# Mini_Ultra_Base_Shield.net
KiCad netlist of a schematic drawn in EAGLE
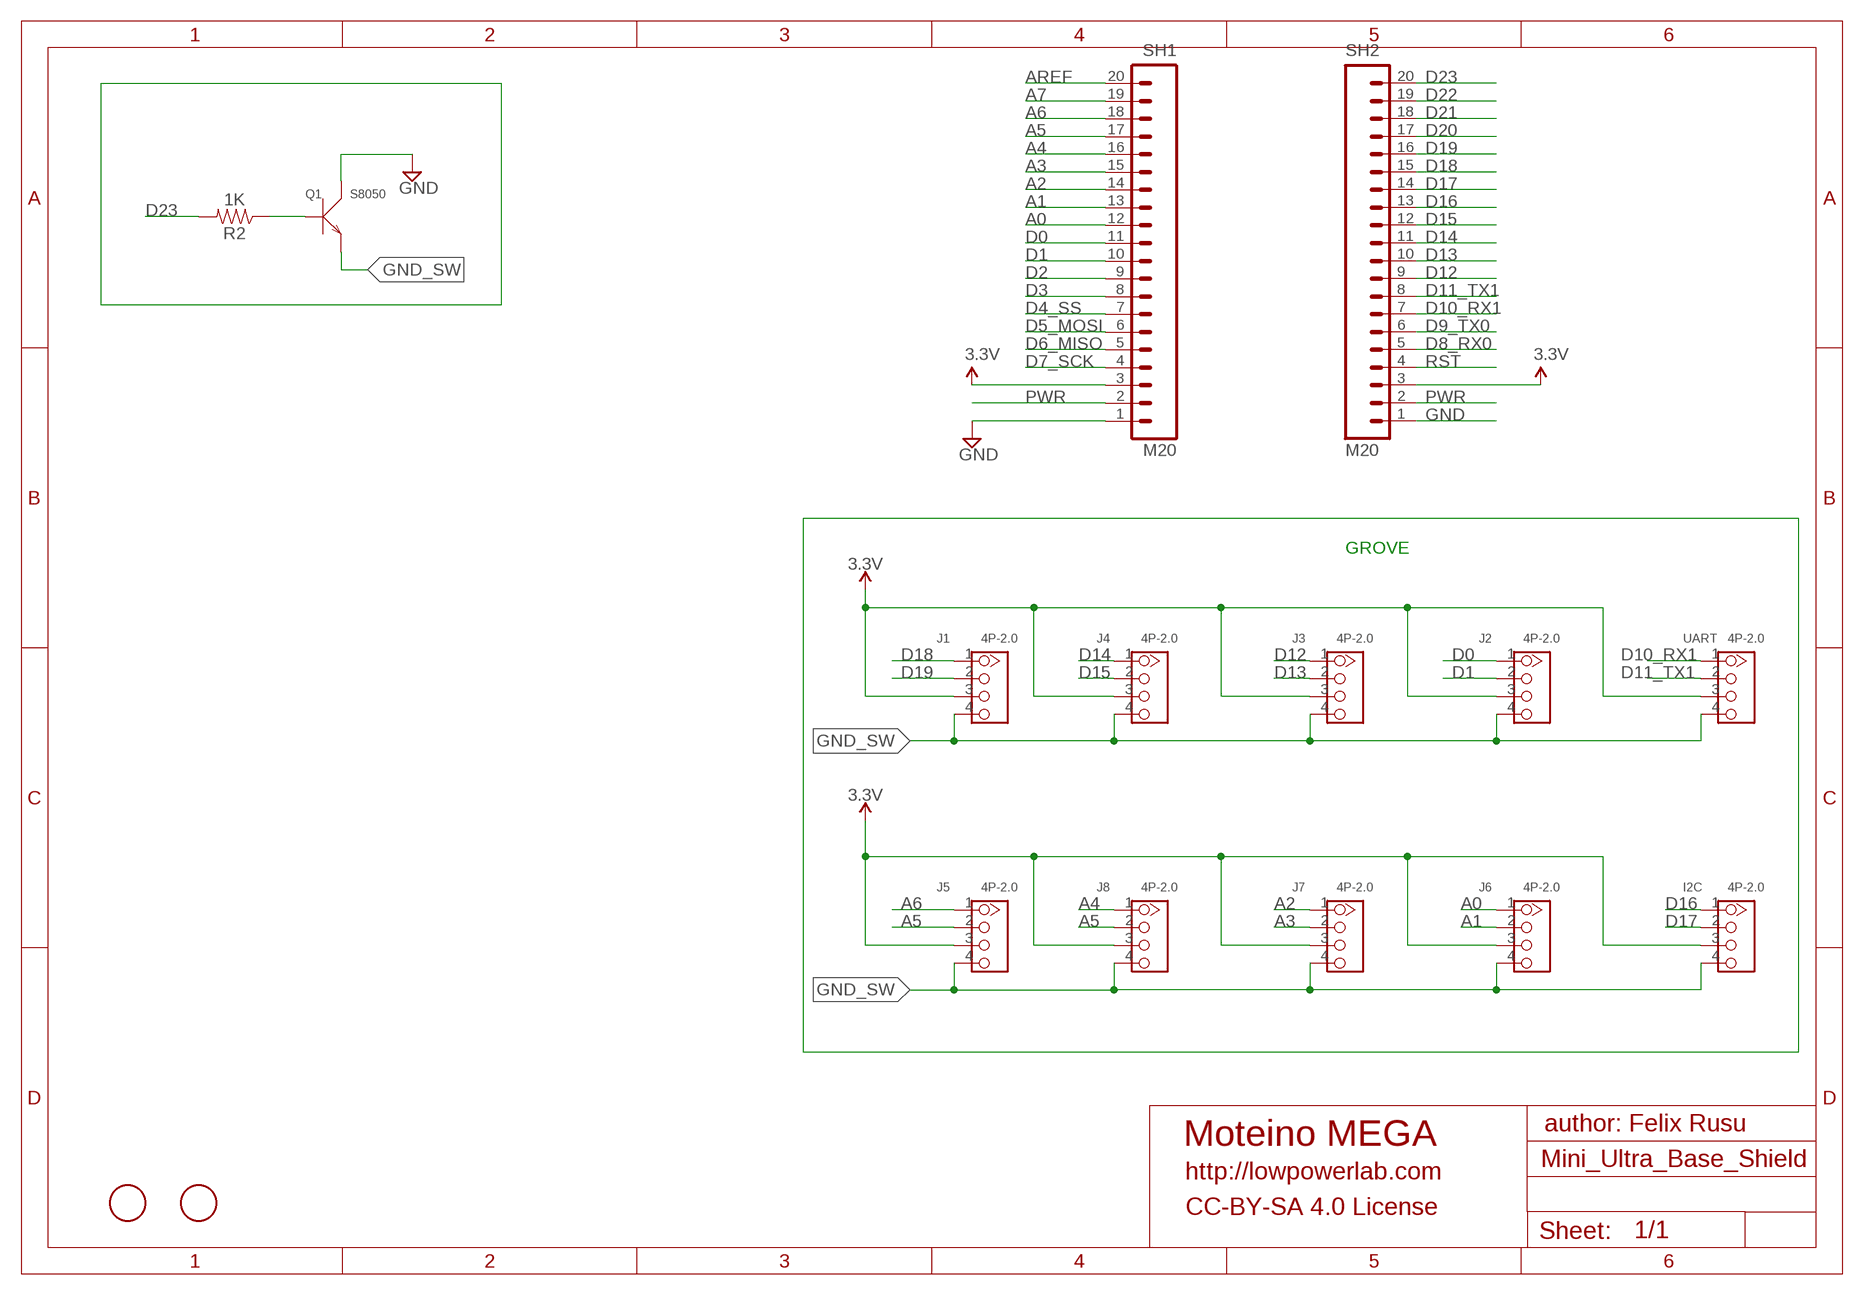
[diagram p0: schematic, sheet 1]

(export (version "E")
  (design (tool "Eeschema 10.0.6"))
  (components
    (comp (ref "I2C")
      (value "4P-2.0")
      (footprint "eagle-import:HW4-2.0")
      (libsource (lib "eagle-import") (part "GROVE-CONNECTOR-DIP(4P-2.0)"))
    )
    (comp (ref "J1")
      (value "4P-2.0")
      (footprint "eagle-import:HW4-2.0")
      (libsource (lib "eagle-import") (part "GROVE-CONNECTOR-DIP(4P-2.0)"))
    )
    (comp (ref "J2")
      (value "4P-2.0")
      (footprint "eagle-import:HW4-2.0")
      (libsource (lib "eagle-import") (part "GROVE-CONNECTOR-DIP(4P-2.0)"))
    )
    (comp (ref "J3")
      (value "4P-2.0")
      (footprint "eagle-import:HW4-2.0")
      (libsource (lib "eagle-import") (part "GROVE-CONNECTOR-DIP(4P-2.0)"))
    )
    (comp (ref "J4")
      (value "4P-2.0")
      (footprint "eagle-import:HW4-2.0")
      (libsource (lib "eagle-import") (part "GROVE-CONNECTOR-DIP(4P-2.0)"))
    )
    (comp (ref "J5")
      (value "4P-2.0")
      (footprint "eagle-import:HW4-2.0")
      (libsource (lib "eagle-import") (part "GROVE-CONNECTOR-DIP(4P-2.0)"))
    )
    (comp (ref "J6")
      (value "4P-2.0")
      (footprint "eagle-import:HW4-2.0")
      (libsource (lib "eagle-import") (part "GROVE-CONNECTOR-DIP(4P-2.0)"))
    )
    (comp (ref "J7")
      (value "4P-2.0")
      (footprint "eagle-import:HW4-2.0")
      (libsource (lib "eagle-import") (part "GROVE-CONNECTOR-DIP(4P-2.0)"))
    )
    (comp (ref "J8")
      (value "4P-2.0")
      (footprint "eagle-import:HW4-2.0")
      (libsource (lib "eagle-import") (part "GROVE-CONNECTOR-DIP(4P-2.0)"))
    )
    (comp (ref "Q1")
      (value "S8050")
      (footprint "eagle-import:SOT-23")
      (libsource (lib "eagle-import") (part "SMD-TRANSISTORS-NPN-25V-500MW-S8050(SOT-23)"))
    )
    (comp (ref "R2")
      (value "1K")
      (footprint "eagle-import:0603")
      (libsource (lib "eagle-import") (part "2.0KOHM-0603-1/10W-5%"))
    )
    (comp (ref "SH1")
      (value "M20")
      (footprint "eagle-import:1X20")
      (libsource (lib "eagle-import") (part "M20"))
    )
    (comp (ref "SH2")
      (value "M20")
      (footprint "eagle-import:1X20")
      (libsource (lib "eagle-import") (part "M20"))
    )
    (comp (ref "U$2")
      (value "FIDUCIAL")
      (footprint "eagle-import:FIDUCIAL_1MM")
      (libsource (lib "eagle-import") (part "FIDUCIAL"))
    )
    (comp (ref "U$7")
      (value "FIDUCIAL")
      (footprint "eagle-import:FIDUCIAL_1MM")
      (libsource (lib "eagle-import") (part "FIDUCIAL"))
    )
    (comp (ref "UART")
      (value "4P-2.0")
      (footprint "eagle-import:HW4-2.0")
      (libsource (lib "eagle-import") (part "GROVE-CONNECTOR-DIP(4P-2.0)"))
    )
  )
  (nets
    (net (code "1") (name "/A0") (class "Default")
      (node (ref "J6") (pin "1") (pinfunction "1_1") (pintype "bidirectional"))
      (node (ref "SH1") (pin "12") (pinfunction "12_12") (pintype "passive"))
    )
    (net (code "2") (name "/A1") (class "Default")
      (node (ref "J6") (pin "2") (pinfunction "2_2") (pintype "bidirectional"))
      (node (ref "SH1") (pin "13") (pinfunction "13_13") (pintype "passive"))
    )
    (net (code "3") (name "/A2") (class "Default")
      (node (ref "J7") (pin "1") (pinfunction "1_1") (pintype "bidirectional"))
      (node (ref "SH1") (pin "14") (pinfunction "14_14") (pintype "passive"))
    )
    (net (code "4") (name "/A3") (class "Default")
      (node (ref "J7") (pin "2") (pinfunction "2_2") (pintype "bidirectional"))
      (node (ref "SH1") (pin "15") (pinfunction "15_15") (pintype "passive"))
    )
    (net (code "5") (name "/A4") (class "Default")
      (node (ref "J8") (pin "1") (pinfunction "1_1") (pintype "bidirectional"))
      (node (ref "SH1") (pin "16") (pinfunction "16_16") (pintype "passive"))
    )
    (net (code "6") (name "/A5") (class "Default")
      (node (ref "J5") (pin "2") (pinfunction "2_2") (pintype "bidirectional"))
      (node (ref "J8") (pin "2") (pinfunction "2_2") (pintype "bidirectional"))
      (node (ref "SH1") (pin "17") (pinfunction "17_17") (pintype "passive"))
    )
    (net (code "7") (name "/A6") (class "Default")
      (node (ref "J5") (pin "1") (pinfunction "1_1") (pintype "bidirectional"))
      (node (ref "SH1") (pin "18") (pinfunction "18_18") (pintype "passive"))
    )
    (net (code "8") (name "/A7") (class "Default")
      (node (ref "SH1") (pin "19") (pinfunction "19_19") (pintype "passive"))
    )
    (net (code "9") (name "/AREF") (class "Default")
      (node (ref "SH1") (pin "20") (pinfunction "20_20") (pintype "passive"))
    )
    (net (code "10") (name "/D0") (class "Default")
      (node (ref "J2") (pin "1") (pinfunction "1_1") (pintype "bidirectional"))
      (node (ref "SH1") (pin "11") (pinfunction "11_11") (pintype "passive"))
    )
    (net (code "11") (name "/D1") (class "Default")
      (node (ref "J2") (pin "2") (pinfunction "2_2") (pintype "bidirectional"))
      (node (ref "SH1") (pin "10") (pinfunction "10_10") (pintype "passive"))
    )
    (net (code "12") (name "/D2") (class "Default")
      (node (ref "SH1") (pin "9") (pinfunction "9_9") (pintype "passive"))
    )
    (net (code "13") (name "/D3") (class "Default")
      (node (ref "SH1") (pin "8") (pinfunction "8_8") (pintype "passive"))
    )
    (net (code "14") (name "/D4_SS") (class "Default")
      (node (ref "SH1") (pin "7") (pinfunction "7_7") (pintype "passive"))
    )
    (net (code "15") (name "/D5_MOSI") (class "Default")
      (node (ref "SH1") (pin "6") (pinfunction "6_6") (pintype "passive"))
    )
    (net (code "16") (name "/D6_MISO") (class "Default")
      (node (ref "SH1") (pin "5") (pinfunction "5_5") (pintype "passive"))
    )
    (net (code "17") (name "/D7_SCK") (class "Default")
      (node (ref "SH1") (pin "4") (pinfunction "4_4") (pintype "passive"))
    )
    (net (code "18") (name "/D8_RX0") (class "Default")
      (node (ref "SH2") (pin "5") (pinfunction "5_5") (pintype "passive"))
    )
    (net (code "19") (name "/D9_TX0") (class "Default")
      (node (ref "SH2") (pin "6") (pinfunction "6_6") (pintype "passive"))
    )
    (net (code "20") (name "/D10_RX1") (class "Default")
      (node (ref "SH2") (pin "7") (pinfunction "7_7") (pintype "passive"))
      (node (ref "UART") (pin "1") (pinfunction "1_1") (pintype "bidirectional"))
    )
    (net (code "21") (name "/D11_TX1") (class "Default")
      (node (ref "SH2") (pin "8") (pinfunction "8_8") (pintype "passive"))
      (node (ref "UART") (pin "2") (pinfunction "2_2") (pintype "bidirectional"))
    )
    (net (code "22") (name "/D12") (class "Default")
      (node (ref "J3") (pin "1") (pinfunction "1_1") (pintype "bidirectional"))
      (node (ref "SH2") (pin "9") (pinfunction "9_9") (pintype "passive"))
    )
    (net (code "23") (name "/D13") (class "Default")
      (node (ref "J3") (pin "2") (pinfunction "2_2") (pintype "bidirectional"))
      (node (ref "SH2") (pin "10") (pinfunction "10_10") (pintype "passive"))
    )
    (net (code "24") (name "/D14") (class "Default")
      (node (ref "J4") (pin "1") (pinfunction "1_1") (pintype "bidirectional"))
      (node (ref "SH2") (pin "11") (pinfunction "11_11") (pintype "passive"))
    )
    (net (code "25") (name "/D15") (class "Default")
      (node (ref "J4") (pin "2") (pinfunction "2_2") (pintype "bidirectional"))
      (node (ref "SH2") (pin "12") (pinfunction "12_12") (pintype "passive"))
    )
    (net (code "26") (name "/D16") (class "Default")
      (node (ref "I2C") (pin "1") (pinfunction "1_1") (pintype "bidirectional"))
      (node (ref "SH2") (pin "13") (pinfunction "13_13") (pintype "passive"))
    )
    (net (code "27") (name "/D17") (class "Default")
      (node (ref "I2C") (pin "2") (pinfunction "2_2") (pintype "bidirectional"))
      (node (ref "SH2") (pin "14") (pinfunction "14_14") (pintype "passive"))
    )
    (net (code "28") (name "/D18") (class "Default")
      (node (ref "J1") (pin "1") (pinfunction "1_1") (pintype "bidirectional"))
      (node (ref "SH2") (pin "15") (pinfunction "15_15") (pintype "passive"))
    )
    (net (code "29") (name "/D19") (class "Default")
      (node (ref "J1") (pin "2") (pinfunction "2_2") (pintype "bidirectional"))
      (node (ref "SH2") (pin "16") (pinfunction "16_16") (pintype "passive"))
    )
    (net (code "30") (name "/D20") (class "Default")
      (node (ref "SH2") (pin "17") (pinfunction "17_17") (pintype "passive"))
    )
    (net (code "31") (name "/D21") (class "Default")
      (node (ref "SH2") (pin "18") (pinfunction "18_18") (pintype "passive"))
    )
    (net (code "32") (name "/D22") (class "Default")
      (node (ref "SH2") (pin "19") (pinfunction "19_19") (pintype "passive"))
    )
    (net (code "33") (name "/D23") (class "Default")
      (node (ref "R2") (pin "2") (pinfunction "2_2") (pintype "passive"))
      (node (ref "SH2") (pin "20") (pinfunction "20_20") (pintype "passive"))
    )
    (net (code "34") (name "/PWR") (class "Default")
      (node (ref "SH1") (pin "2") (pinfunction "2_2") (pintype "passive"))
      (node (ref "SH2") (pin "2") (pinfunction "2_2") (pintype "passive"))
    )
    (net (code "35") (name "/RST") (class "Default")
      (node (ref "SH2") (pin "4") (pinfunction "4_4") (pintype "passive"))
    )
    (net (code "36") (name "3.3V") (class "Default")
      (node (ref "I2C") (pin "3") (pinfunction "3_3") (pintype "bidirectional"))
      (node (ref "J1") (pin "3") (pinfunction "3_3") (pintype "bidirectional"))
      (node (ref "J2") (pin "3") (pinfunction "3_3") (pintype "bidirectional"))
      (node (ref "J3") (pin "3") (pinfunction "3_3") (pintype "bidirectional"))
      (node (ref "J4") (pin "3") (pinfunction "3_3") (pintype "bidirectional"))
      (node (ref "J5") (pin "3") (pinfunction "3_3") (pintype "bidirectional"))
      (node (ref "J6") (pin "3") (pinfunction "3_3") (pintype "bidirectional"))
      (node (ref "J7") (pin "3") (pinfunction "3_3") (pintype "bidirectional"))
      (node (ref "J8") (pin "3") (pinfunction "3_3") (pintype "bidirectional"))
      (node (ref "SH1") (pin "3") (pinfunction "3_3") (pintype "passive"))
      (node (ref "SH2") (pin "3") (pinfunction "3_3") (pintype "passive"))
      (node (ref "UART") (pin "3") (pinfunction "3_3") (pintype "bidirectional"))
    )
    (net (code "37") (name "GND") (class "Default")
      (node (ref "Q1") (pin "3") (pinfunction "C_3") (pintype "passive"))
      (node (ref "SH1") (pin "1") (pinfunction "1_1") (pintype "passive"))
      (node (ref "SH2") (pin "1") (pinfunction "1_1") (pintype "passive"))
    )
    (net (code "38") (name "GND_SW") (class "Default")
      (node (ref "I2C") (pin "4") (pinfunction "4_4") (pintype "bidirectional"))
      (node (ref "J1") (pin "4") (pinfunction "4_4") (pintype "bidirectional"))
      (node (ref "J2") (pin "4") (pinfunction "4_4") (pintype "bidirectional"))
      (node (ref "J3") (pin "4") (pinfunction "4_4") (pintype "bidirectional"))
      (node (ref "J4") (pin "4") (pinfunction "4_4") (pintype "bidirectional"))
      (node (ref "J5") (pin "4") (pinfunction "4_4") (pintype "bidirectional"))
      (node (ref "J6") (pin "4") (pinfunction "4_4") (pintype "bidirectional"))
      (node (ref "J7") (pin "4") (pinfunction "4_4") (pintype "bidirectional"))
      (node (ref "J8") (pin "4") (pinfunction "4_4") (pintype "bidirectional"))
      (node (ref "Q1") (pin "2") (pinfunction "E_2") (pintype "passive"))
      (node (ref "UART") (pin "4") (pinfunction "4_4") (pintype "bidirectional"))
    )
    (net (code "39") (name "Net-(Q1-B)") (class "Default")
      (node (ref "Q1") (pin "1") (pinfunction "B_1") (pintype "passive"))
      (node (ref "R2") (pin "1") (pinfunction "1_1") (pintype "passive"))
    )
  )
)
